# Supply.net
KiCad netlist of a schematic drawn in Altium Designer
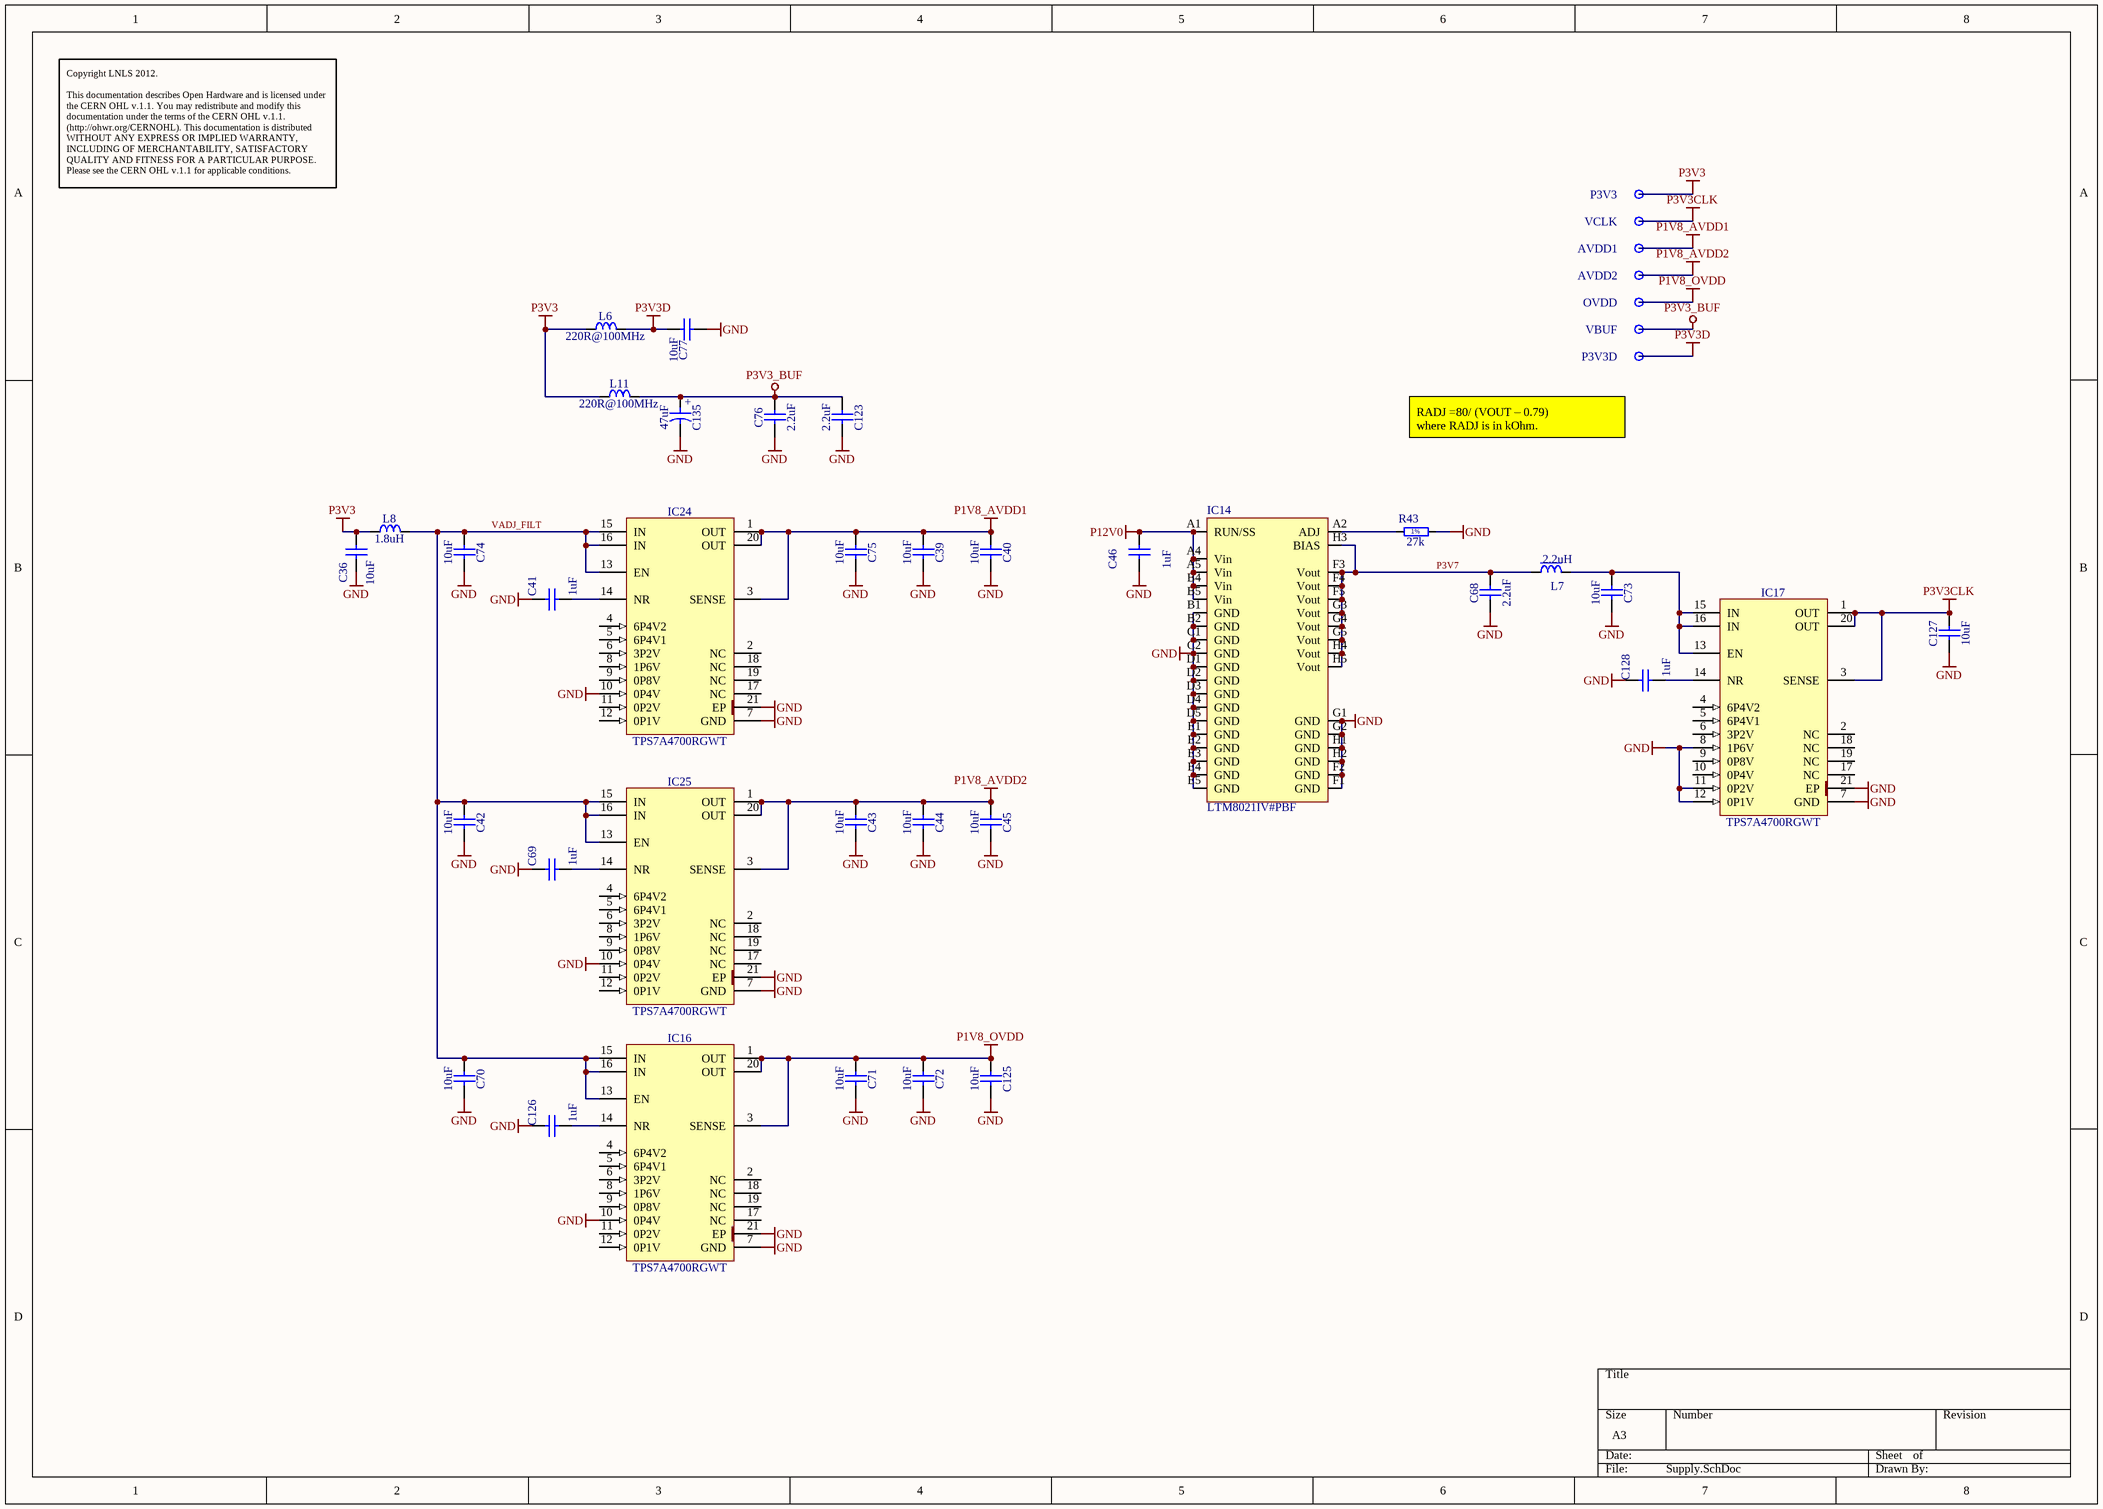
[diagram p0: Supply.SchDoc]

(export (version "E")
  (design (tool "Eeschema 10.0.6"))
  (components
    (comp (ref "AVDD1")
      (value "Test Point")
      (footprint "TPS127")
      (fields (field (name "PART NUMBER") "SMD_PAD_1.27X1.27MM") (field (name "AUTHOR") "CERN DEM JLC"))
      (libsource (lib "Eletro-mechanical") (part "Test Point"))
    )
    (comp (ref "AVDD2")
      (value "Test Point")
      (footprint "TPS127")
      (fields (field (name "PART NUMBER") "SMD_PAD_1.27X1.27MM") (field (name "AUTHOR") "CERN DEM JLC"))
      (libsource (lib "Eletro-mechanical") (part "Test Point"))
    )
    (comp (ref "C36")
      (value "10uF")
      (footprint "CAPC2012X135N")
      (description "Non-polarised capacitor")
      (fields
        (field (name "PART NUMBER") "CC0805_10UF_16V_10%_X5R")
        (field (name "VOLTAGE") "16V")
        (field (name "AUTHOR") "CERN DEM JLC")
      )
      (libsource (lib "Capacitors") (part "Capacitor - non polarized"))
    )
    (comp (ref "C39")
      (value "10uF")
      (footprint "CAPC2012X135N")
      (description "Non-polarised capacitor")
      (fields
        (field (name "PART NUMBER") "CC0805_10UF_16V_10%_X5R")
        (field (name "VOLTAGE") "16V")
        (field (name "AUTHOR") "CERN DEM JLC")
      )
      (libsource (lib "Capacitors") (part "Capacitor - non polarized"))
    )
    (comp (ref "C40")
      (value "10uF")
      (footprint "CAPC2012X135N")
      (description "Non-polarised capacitor")
      (fields
        (field (name "PART NUMBER") "CC0805_10UF_16V_10%_X5R")
        (field (name "VOLTAGE") "16V")
        (field (name "AUTHOR") "CERN DEM JLC")
      )
      (libsource (lib "Capacitors") (part "Capacitor - non polarized"))
    )
    (comp (ref "C41")
      (value "1uF")
      (footprint "CAPC1608X87N")
      (description "Non-polarised capacitor")
      (fields
        (field (name "PART NUMBER") "CC0603_1UF_16V_10%_X7R")
        (field (name "VOLTAGE") "16V")
        (field (name "AUTHOR") "CERN DEM JLC")
      )
      (libsource (lib "Capacitors") (part "Capacitor - non polarized"))
    )
    (comp (ref "C42")
      (value "10uF")
      (footprint "CAPC2012X135N")
      (description "Non-polarised capacitor")
      (fields
        (field (name "PART NUMBER") "CC0805_10UF_16V_10%_X5R")
        (field (name "VOLTAGE") "16V")
        (field (name "AUTHOR") "CERN DEM JLC")
      )
      (libsource (lib "Capacitors") (part "Capacitor - non polarized"))
    )
    (comp (ref "C43")
      (value "10uF")
      (footprint "CAPC2012X135N")
      (description "Non-polarised capacitor")
      (fields
        (field (name "PART NUMBER") "CC0805_10UF_16V_10%_X5R")
        (field (name "VOLTAGE") "16V")
        (field (name "AUTHOR") "CERN DEM JLC")
      )
      (libsource (lib "Capacitors") (part "Capacitor - non polarized"))
    )
    (comp (ref "C44")
      (value "10uF")
      (footprint "CAPC2012X135N")
      (description "Non-polarised capacitor")
      (fields
        (field (name "PART NUMBER") "CC0805_10UF_16V_10%_X5R")
        (field (name "VOLTAGE") "16V")
        (field (name "AUTHOR") "CERN DEM JLC")
      )
      (libsource (lib "Capacitors") (part "Capacitor - non polarized"))
    )
    (comp (ref "C45")
      (value "10uF")
      (footprint "CAPC2012X135N")
      (description "Non-polarised capacitor")
      (fields
        (field (name "PART NUMBER") "CC0805_10UF_16V_10%_X5R")
        (field (name "VOLTAGE") "16V")
        (field (name "AUTHOR") "CERN DEM JLC")
      )
      (libsource (lib "Capacitors") (part "Capacitor - non polarized"))
    )
    (comp (ref "C46")
      (value "1uF")
      (footprint "CAPC1608X87N")
      (description "Non-polarised capacitor")
      (fields
        (field (name "PART NUMBER") "CC0603_1UF_16V_10%_X7R")
        (field (name "VOLTAGE") "16V")
        (field (name "AUTHOR") "CERN DEM JLC")
      )
      (libsource (lib "Capacitors") (part "Capacitor - non polarized"))
    )
    (comp (ref "C68")
      (value "2.2uF")
      (footprint "CAPC2012X135N")
      (description "Non-polarised capacitor")
      (fields
        (field (name "PART NUMBER") "CC0805_2.2UF_16V_10%_X7R")
        (field (name "VOLTAGE") "16V")
        (field (name "AUTHOR") "CERN DEM JLC")
      )
      (libsource (lib "Capacitors") (part "Capacitor - non polarized"))
    )
    (comp (ref "C69")
      (value "1uF")
      (footprint "CAPC1608X87N")
      (description "Non-polarised capacitor")
      (fields
        (field (name "PART NUMBER") "CC0603_1UF_16V_10%_X7R")
        (field (name "VOLTAGE") "16V")
        (field (name "AUTHOR") "CERN DEM JLC")
      )
      (libsource (lib "Capacitors") (part "Capacitor - non polarized"))
    )
    (comp (ref "C70")
      (value "10uF")
      (footprint "CAPC2012X135N")
      (description "Non-polarised capacitor")
      (fields
        (field (name "PART NUMBER") "CC0805_10UF_16V_10%_X5R")
        (field (name "VOLTAGE") "16V")
        (field (name "AUTHOR") "CERN DEM JLC")
      )
      (libsource (lib "Capacitors") (part "Capacitor - non polarized"))
    )
    (comp (ref "C71")
      (value "10uF")
      (footprint "CAPC2012X135N")
      (description "Non-polarised capacitor")
      (fields
        (field (name "PART NUMBER") "CC0805_10UF_16V_10%_X5R")
        (field (name "VOLTAGE") "16V")
        (field (name "AUTHOR") "CERN DEM JLC")
      )
      (libsource (lib "Capacitors") (part "Capacitor - non polarized"))
    )
    (comp (ref "C72")
      (value "10uF")
      (footprint "CAPC2012X135N")
      (description "Non-polarised capacitor")
      (fields
        (field (name "PART NUMBER") "CC0805_10UF_16V_10%_X5R")
        (field (name "VOLTAGE") "16V")
        (field (name "AUTHOR") "CERN DEM JLC")
      )
      (libsource (lib "Capacitors") (part "Capacitor - non polarized"))
    )
    (comp (ref "C73")
      (value "10uF")
      (footprint "CAPC2012X135N")
      (description "Non-polarised capacitor")
      (fields
        (field (name "PART NUMBER") "CC0805_10UF_16V_10%_X5R")
        (field (name "VOLTAGE") "16V")
        (field (name "AUTHOR") "CERN DEM JLC")
      )
      (libsource (lib "Capacitors") (part "Capacitor - non polarized"))
    )
    (comp (ref "C74")
      (value "10uF")
      (footprint "CAPC2012X135N")
      (description "Non-polarised capacitor")
      (fields
        (field (name "PART NUMBER") "CC0805_10UF_16V_10%_X5R")
        (field (name "VOLTAGE") "16V")
        (field (name "AUTHOR") "CERN DEM JLC")
      )
      (libsource (lib "Capacitors") (part "Capacitor - non polarized"))
    )
    (comp (ref "C75")
      (value "10uF")
      (footprint "CAPC2012X135N")
      (description "Non-polarised capacitor")
      (fields
        (field (name "PART NUMBER") "CC0805_10UF_16V_10%_X5R")
        (field (name "VOLTAGE") "16V")
        (field (name "AUTHOR") "CERN DEM JLC")
      )
      (libsource (lib "Capacitors") (part "Capacitor - non polarized"))
    )
    (comp (ref "C76")
      (value "2.2uF")
      (footprint "CAPC2012X135N")
      (description "Non-polarised capacitor")
      (fields
        (field (name "PART NUMBER") "CC0805_2.2UF_16V_10%_X7R")
        (field (name "VOLTAGE") "16V")
        (field (name "AUTHOR") "CERN DEM JLC")
      )
      (libsource (lib "Capacitors") (part "Capacitor - non polarized"))
    )
    (comp (ref "C77")
      (value "10uF")
      (footprint "CAPC2012X135N")
      (description "Non-polarised capacitor")
      (fields
        (field (name "PART NUMBER") "CC0805_10UF_16V_10%_X5R")
        (field (name "VOLTAGE") "16V")
        (field (name "AUTHOR") "CERN DEM JLC")
      )
      (libsource (lib "Capacitors") (part "Capacitor - non polarized"))
    )
    (comp (ref "C123")
      (value "2.2uF")
      (footprint "CAPC2012X135N")
      (description "Non-polarised capacitor")
      (fields
        (field (name "PART NUMBER") "CC0805_2.2UF_16V_10%_X7R")
        (field (name "VOLTAGE") "16V")
        (field (name "AUTHOR") "CERN DEM JLC")
      )
      (libsource (lib "Capacitors") (part "Capacitor - non polarized"))
    )
    (comp (ref "C125")
      (value "10uF")
      (footprint "CAPC2012X135N")
      (description "Non-polarised capacitor")
      (fields
        (field (name "PART NUMBER") "CC0805_10UF_16V_10%_X5R")
        (field (name "VOLTAGE") "16V")
        (field (name "AUTHOR") "CERN DEM JLC")
      )
      (libsource (lib "Capacitors") (part "Capacitor - non polarized"))
    )
    (comp (ref "C126")
      (value "1uF")
      (footprint "CAPC1608X87N")
      (description "Non-polarised capacitor")
      (fields
        (field (name "PART NUMBER") "CC0603_1UF_16V_10%_X7R")
        (field (name "VOLTAGE") "16V")
        (field (name "AUTHOR") "CERN DEM JLC")
      )
      (libsource (lib "Capacitors") (part "Capacitor - non polarized"))
    )
    (comp (ref "C127")
      (value "10uF")
      (footprint "CAPC2012X135N")
      (description "Non-polarised capacitor")
      (fields
        (field (name "PART NUMBER") "CC0805_10UF_16V_10%_X5R")
        (field (name "VOLTAGE") "16V")
        (field (name "AUTHOR") "CERN DEM JLC")
      )
      (libsource (lib "Capacitors") (part "Capacitor - non polarized"))
    )
    (comp (ref "C128")
      (value "1uF")
      (footprint "CAPC1608X87N")
      (description "Non-polarised capacitor")
      (fields
        (field (name "PART NUMBER") "CC0603_1UF_16V_10%_X7R")
        (field (name "VOLTAGE") "16V")
        (field (name "AUTHOR") "CERN DEM JLC")
      )
      (libsource (lib "Capacitors") (part "Capacitor - non polarized"))
    )
    (comp (ref "C135")
      (value "47uF")
      (footprint "CAPMP3528X210N")
      (description "Polarised capacitor")
      (fields
        (field (name "PART NUMBER") "CTE3528-21_47UF_6.3V_10%_LESR0250")
        (field (name "VOLTAGE") "6.3V")
        (field (name "AUTHOR") "CERN DEM JLC")
      )
      (libsource (lib "Capacitors") (part "Capacitor - polarized"))
    )
    (comp (ref "IC14")
      (value "LTM8021IV#PBF")
      (footprint "LGA35S127P5X8_625x1125x292")
      (description "36VIN, 500mA  Step-Down DC/DC Module")
      (fields (field (name "MANUFACTURER") "LINEAR TECHNOLOGY") (field (name "AUTHOR") "LNLS DIG GBMB"))
      (libsource (lib "ICs And Semiconductors_LNLS") (part "DCDC_LINEAR_LTM8021"))
    )
    (comp (ref "IC16")
      (value "TPS7A4700RGWT")
      (footprint "QFN65P500X500X100-21N-S325")
      (description "Low Noise (3uVrms), 1A, High Voltage Low-Dropout Linear Regulator")
      (fields (field (name "MANUFACTURER") "TEXAS INSTRUMENTS") (field (name "AUTHOR") "CERN DEM JLC"))
      (libsource (lib "ICs And Semiconductors") (part "TPS7A4700RGW"))
    )
    (comp (ref "IC17")
      (value "TPS7A4700RGWT")
      (footprint "QFN65P500X500X100-21N-S325")
      (description "Low Noise (3uVrms), 1A, High Voltage Low-Dropout Linear Regulator")
      (fields (field (name "MANUFACTURER") "TEXAS INSTRUMENTS") (field (name "AUTHOR") "CERN DEM JLC"))
      (libsource (lib "ICs And Semiconductors") (part "TPS7A4700RGW"))
    )
    (comp (ref "IC24")
      (value "TPS7A4700RGWT")
      (footprint "QFN65P500X500X100-21N-S325")
      (description "Low Noise (3uVrms), 1A, High Voltage Low-Dropout Linear Regulator")
      (fields (field (name "MANUFACTURER") "TEXAS INSTRUMENTS") (field (name "AUTHOR") "CERN DEM JLC"))
      (libsource (lib "ICs And Semiconductors") (part "TPS7A4700RGW"))
    )
    (comp (ref "IC25")
      (value "TPS7A4700RGWT")
      (footprint "QFN65P500X500X100-21N-S325")
      (description "Low Noise (3uVrms), 1A, High Voltage Low-Dropout Linear Regulator")
      (fields (field (name "MANUFACTURER") "TEXAS INSTRUMENTS") (field (name "AUTHOR") "CERN DEM JLC"))
      (libsource (lib "ICs And Semiconductors") (part "TPS7A4700RGW"))
    )
    (comp (ref "L6")
      (value "220R@100MHz")
      (footprint "INDC2012X105N")
      (description "Inductor")
      (fields
        (field (name "PART NUMBER") "IND0805_MURATA_BLM21PG221SN1D")
        (field (name "POWER") "2A")
        (field (name "AUTHOR") "CERN DEM JLC")
      )
      (libsource (lib "Inductors & Transformers") (part "Inductor"))
    )
    (comp (ref "L7")
      (value "2.2uH")
      (footprint "IND_PANASONIC_ELLVGG")
      (description "Inductor With Core")
      (fields
        (field (name "PART NUMBER") "IND_2.2UH_30%_PANASONIC_ELLVGG2R2N")
        (field (name "POWER") "1.4A")
        (field (name "AUTHOR") "LNLS DIG GBMB")
      )
      (libsource (lib "Inductors & Transformers_LNLS") (part "Inductor With Magnetic core"))
    )
    (comp (ref "L8")
      (value "1.8uH")
      (footprint "IND_TDK_VLCF4020-1-1.8uH")
      (description "Inductor")
      (fields
        (field (name "PART NUMBER") "IND_1.8UH_30%_TDK_VLCF4020-1")
        (field (name "POWER") "1.9A")
        (field (name "AUTHOR") "LNLS DIG LOS")
      )
      (libsource (lib "Inductors & Transformers_LNLS") (part "Inductor"))
    )
    (comp (ref "L11")
      (value "220R@100MHz")
      (footprint "INDC2012X105N")
      (description "Inductor")
      (fields
        (field (name "PART NUMBER") "IND0805_MURATA_BLM21PG221SN1D")
        (field (name "POWER") "2A")
        (field (name "AUTHOR") "CERN DEM JLC")
      )
      (libsource (lib "Inductors & Transformers") (part "Inductor"))
    )
    (comp (ref "OVDD")
      (value "Test Point")
      (footprint "TPS127")
      (fields (field (name "PART NUMBER") "SMD_PAD_1.27X1.27MM") (field (name "AUTHOR") "CERN DEM JLC"))
      (libsource (lib "Eletro-mechanical") (part "Test Point"))
    )
    (comp (ref "P3V3")
      (value "Test Point")
      (footprint "TPS127")
      (fields (field (name "PART NUMBER") "SMD_PAD_1.27X1.27MM") (field (name "AUTHOR") "CERN DEM JLC"))
      (libsource (lib "Eletro-mechanical") (part "Test Point"))
    )
    (comp (ref "P3V3D")
      (value "Test Point")
      (footprint "TPS127")
      (fields (field (name "PART NUMBER") "SMD_PAD_1.27X1.27MM") (field (name "AUTHOR") "CERN DEM JLC"))
      (libsource (lib "Eletro-mechanical") (part "Test Point"))
    )
    (comp (ref "R43")
      (value "27k")
      (footprint "RESC1608X55N")
      (description "Resistor - 1%")
      (fields
        (field (name "PART NUMBER") "R0603_27K_1%_0.1W_100PPM")
        (field (name "POWER") "0.1W")
        (field (name "AUTHOR") "CERN DEM JLC")
      )
      (libsource (lib "Resistors") (part "Resistor - 1%"))
    )
    (comp (ref "VBUF")
      (value "Test Point")
      (footprint "TPS127")
      (fields (field (name "PART NUMBER") "SMD_PAD_1.27X1.27MM") (field (name "AUTHOR") "CERN DEM JLC"))
      (libsource (lib "Eletro-mechanical") (part "Test Point"))
    )
    (comp (ref "VCLK")
      (value "Test Point")
      (footprint "TPS127")
      (fields (field (name "PART NUMBER") "SMD_PAD_1.27X1.27MM") (field (name "AUTHOR") "CERN DEM JLC"))
      (libsource (lib "Eletro-mechanical") (part "Test Point"))
    )
  )
  (nets
    (net (code "1") (name "/P3V7") (class "Default")
      (node (ref "C68") (pin "2") (pinfunction "2_2") (pintype "passive"))
      (node (ref "IC14") (pin "F3") (pinfunction "Vout_F3") (pintype "passive"))
      (node (ref "IC14") (pin "F4") (pinfunction "Vout_F4") (pintype "passive"))
      (node (ref "IC14") (pin "F5") (pinfunction "Vout_F5") (pintype "passive"))
      (node (ref "IC14") (pin "G3") (pinfunction "Vout_G3") (pintype "passive"))
      (node (ref "IC14") (pin "G4") (pinfunction "Vout_G4") (pintype "passive"))
      (node (ref "IC14") (pin "G5") (pinfunction "Vout_G5") (pintype "passive"))
      (node (ref "IC14") (pin "H3") (pinfunction "BIAS_H3") (pintype "power_in"))
      (node (ref "IC14") (pin "H4") (pinfunction "Vout_H4") (pintype "passive"))
      (node (ref "IC14") (pin "H5") (pinfunction "Vout_H5") (pintype "passive"))
      (node (ref "L7") (pin "1") (pinfunction "1_1") (pintype "passive"))
    )
    (net (code "2") (name "/VADJ_FILT") (class "Default")
      (node (ref "C42") (pin "1") (pinfunction "1_1") (pintype "passive"))
      (node (ref "C70") (pin "1") (pinfunction "1_1") (pintype "passive"))
      (node (ref "C74") (pin "1") (pinfunction "1_1") (pintype "passive"))
      (node (ref "IC16") (pin "13") (pinfunction "EN_13") (pintype "passive"))
      (node (ref "IC16") (pin "15") (pinfunction "IN_15") (pintype "power_in"))
      (node (ref "IC16") (pin "16") (pinfunction "IN_16") (pintype "power_in"))
      (node (ref "IC24") (pin "13") (pinfunction "EN_13") (pintype "passive"))
      (node (ref "IC24") (pin "15") (pinfunction "IN_15") (pintype "power_in"))
      (node (ref "IC24") (pin "16") (pinfunction "IN_16") (pintype "power_in"))
      (node (ref "IC25") (pin "13") (pinfunction "EN_13") (pintype "passive"))
      (node (ref "IC25") (pin "15") (pinfunction "IN_15") (pintype "power_in"))
      (node (ref "IC25") (pin "16") (pinfunction "IN_16") (pintype "power_in"))
      (node (ref "L8") (pin "2") (pinfunction "2_2") (pintype "passive"))
    )
    (net (code "3") (name "GND") (class "Default")
      (node (ref "C123") (pin "2") (pinfunction "2_2") (pintype "passive"))
      (node (ref "C125") (pin "2") (pinfunction "2_2") (pintype "passive"))
      (node (ref "C126") (pin "2") (pinfunction "2_2") (pintype "passive"))
      (node (ref "C127") (pin "1") (pinfunction "1_1") (pintype "passive"))
      (node (ref "C128") (pin "2") (pinfunction "2_2") (pintype "passive"))
      (node (ref "C135") (pin "2") (pinfunction "2_2") (pintype "passive"))
      (node (ref "C36") (pin "2") (pinfunction "2_2") (pintype "passive"))
      (node (ref "C39") (pin "2") (pinfunction "2_2") (pintype "passive"))
      (node (ref "C40") (pin "2") (pinfunction "2_2") (pintype "passive"))
      (node (ref "C41") (pin "2") (pinfunction "2_2") (pintype "passive"))
      (node (ref "C42") (pin "2") (pinfunction "2_2") (pintype "passive"))
      (node (ref "C43") (pin "2") (pinfunction "2_2") (pintype "passive"))
      (node (ref "C44") (pin "2") (pinfunction "2_2") (pintype "passive"))
      (node (ref "C45") (pin "2") (pinfunction "2_2") (pintype "passive"))
      (node (ref "C46") (pin "2") (pinfunction "2_2") (pintype "passive"))
      (node (ref "C68") (pin "1") (pinfunction "1_1") (pintype "passive"))
      (node (ref "C69") (pin "2") (pinfunction "2_2") (pintype "passive"))
      (node (ref "C70") (pin "2") (pinfunction "2_2") (pintype "passive"))
      (node (ref "C71") (pin "2") (pinfunction "2_2") (pintype "passive"))
      (node (ref "C72") (pin "2") (pinfunction "2_2") (pintype "passive"))
      (node (ref "C73") (pin "2") (pinfunction "2_2") (pintype "passive"))
      (node (ref "C74") (pin "2") (pinfunction "2_2") (pintype "passive"))
      (node (ref "C75") (pin "2") (pinfunction "2_2") (pintype "passive"))
      (node (ref "C76") (pin "1") (pinfunction "1_1") (pintype "passive"))
      (node (ref "C77") (pin "2") (pinfunction "2_2") (pintype "passive"))
      (node (ref "IC14") (pin "B1") (pinfunction "GND_B1") (pintype "power_in"))
      (node (ref "IC14") (pin "B2") (pinfunction "GND_B2") (pintype "power_in"))
      (node (ref "IC14") (pin "C1") (pinfunction "GND_C1") (pintype "power_in"))
      (node (ref "IC14") (pin "C2") (pinfunction "GND_C2") (pintype "power_in"))
      (node (ref "IC14") (pin "D1") (pinfunction "GND_D1") (pintype "power_in"))
      (node (ref "IC14") (pin "D2") (pinfunction "GND_D2") (pintype "power_in"))
      (node (ref "IC14") (pin "D3") (pinfunction "GND_D3") (pintype "power_in"))
      (node (ref "IC14") (pin "D4") (pinfunction "GND_D4") (pintype "power_in"))
      (node (ref "IC14") (pin "D5") (pinfunction "GND_D5") (pintype "power_in"))
      (node (ref "IC14") (pin "E1") (pinfunction "GND_E1") (pintype "power_in"))
      (node (ref "IC14") (pin "E2") (pinfunction "GND_E2") (pintype "power_in"))
      (node (ref "IC14") (pin "E3") (pinfunction "GND_E3") (pintype "power_in"))
      (node (ref "IC14") (pin "E4") (pinfunction "GND_E4") (pintype "power_in"))
      (node (ref "IC14") (pin "E5") (pinfunction "GND_E5") (pintype "power_in"))
      (node (ref "IC14") (pin "F1") (pinfunction "GND_F1") (pintype "power_in"))
      (node (ref "IC14") (pin "F2") (pinfunction "GND_F2") (pintype "power_in"))
      (node (ref "IC14") (pin "G1") (pinfunction "GND_G1") (pintype "power_in"))
      (node (ref "IC14") (pin "G2") (pinfunction "GND_G2") (pintype "power_in"))
      (node (ref "IC14") (pin "H1") (pinfunction "GND_H1") (pintype "power_in"))
      (node (ref "IC14") (pin "H2") (pinfunction "GND_H2") (pintype "power_in"))
      (node (ref "IC16") (pin "10") (pinfunction "0P4V_10") (pintype "input"))
      (node (ref "IC16") (pin "21") (pinfunction "EP_21") (pintype "power_in"))
      (node (ref "IC16") (pin "7") (pinfunction "GND_7") (pintype "power_in"))
      (node (ref "IC17") (pin "11") (pinfunction "0P2V_11") (pintype "input"))
      (node (ref "IC17") (pin "12") (pinfunction "0P1V_12") (pintype "input"))
      (node (ref "IC17") (pin "21") (pinfunction "EP_21") (pintype "power_in"))
      (node (ref "IC17") (pin "7") (pinfunction "GND_7") (pintype "power_in"))
      (node (ref "IC17") (pin "8") (pinfunction "1P6V_8") (pintype "input"))
      (node (ref "IC24") (pin "10") (pinfunction "0P4V_10") (pintype "input"))
      (node (ref "IC24") (pin "21") (pinfunction "EP_21") (pintype "power_in"))
      (node (ref "IC24") (pin "7") (pinfunction "GND_7") (pintype "power_in"))
      (node (ref "IC25") (pin "10") (pinfunction "0P4V_10") (pintype "input"))
      (node (ref "IC25") (pin "21") (pinfunction "EP_21") (pintype "power_in"))
      (node (ref "IC25") (pin "7") (pinfunction "GND_7") (pintype "power_in"))
      (node (ref "R43") (pin "2") (pinfunction "2_2") (pintype "passive"))
    )
    (net (code "4") (name "Net-(IC14-ADJ)") (class "Default")
      (node (ref "IC14") (pin "A2") (pinfunction "ADJ_A2") (pintype "passive"))
      (node (ref "R43") (pin "1") (pinfunction "1_1") (pintype "passive"))
    )
    (net (code "5") (name "Net-(IC16-NR)") (class "Default")
      (node (ref "C126") (pin "1") (pinfunction "1_1") (pintype "passive"))
      (node (ref "IC16") (pin "14") (pinfunction "NR_14") (pintype "passive"))
    )
    (net (code "6") (name "Net-(IC17-EN)") (class "Default")
      (node (ref "C73") (pin "1") (pinfunction "1_1") (pintype "passive"))
      (node (ref "IC17") (pin "13") (pinfunction "EN_13") (pintype "passive"))
      (node (ref "IC17") (pin "15") (pinfunction "IN_15") (pintype "power_in"))
      (node (ref "IC17") (pin "16") (pinfunction "IN_16") (pintype "power_in"))
      (node (ref "L7") (pin "2") (pinfunction "2_2") (pintype "passive"))
    )
    (net (code "7") (name "Net-(IC17-NR)") (class "Default")
      (node (ref "C128") (pin "1") (pinfunction "1_1") (pintype "passive"))
      (node (ref "IC17") (pin "14") (pinfunction "NR_14") (pintype "passive"))
    )
    (net (code "8") (name "Net-(IC24-NR)") (class "Default")
      (node (ref "C41") (pin "1") (pinfunction "1_1") (pintype "passive"))
      (node (ref "IC24") (pin "14") (pinfunction "NR_14") (pintype "passive"))
    )
    (net (code "9") (name "Net-(IC25-NR)") (class "Default")
      (node (ref "C69") (pin "1") (pinfunction "1_1") (pintype "passive"))
      (node (ref "IC25") (pin "14") (pinfunction "NR_14") (pintype "passive"))
    )
    (net (code "10") (name "P1V8_AVDD1") (class "Default")
      (node (ref "AVDD1") (pin "1") (pinfunction "1_1") (pintype "bidirectional"))
      (node (ref "C39") (pin "1") (pinfunction "1_1") (pintype "passive"))
      (node (ref "C40") (pin "1") (pinfunction "1_1") (pintype "passive"))
      (node (ref "C75") (pin "1") (pinfunction "1_1") (pintype "passive"))
      (node (ref "IC24") (pin "1") (pinfunction "OUT_1") (pintype "power_in"))
      (node (ref "IC24") (pin "20") (pinfunction "OUT_20") (pintype "power_in"))
      (node (ref "IC24") (pin "3") (pinfunction "SENSE_3") (pintype "passive"))
    )
    (net (code "11") (name "P1V8_AVDD2") (class "Default")
      (node (ref "AVDD2") (pin "1") (pinfunction "1_1") (pintype "bidirectional"))
      (node (ref "C43") (pin "1") (pinfunction "1_1") (pintype "passive"))
      (node (ref "C44") (pin "1") (pinfunction "1_1") (pintype "passive"))
      (node (ref "C45") (pin "1") (pinfunction "1_1") (pintype "passive"))
      (node (ref "IC25") (pin "1") (pinfunction "OUT_1") (pintype "power_in"))
      (node (ref "IC25") (pin "20") (pinfunction "OUT_20") (pintype "power_in"))
      (node (ref "IC25") (pin "3") (pinfunction "SENSE_3") (pintype "passive"))
    )
    (net (code "12") (name "P1V8_OVDD") (class "Default")
      (node (ref "C125") (pin "1") (pinfunction "1_1") (pintype "passive"))
      (node (ref "C71") (pin "1") (pinfunction "1_1") (pintype "passive"))
      (node (ref "C72") (pin "1") (pinfunction "1_1") (pintype "passive"))
      (node (ref "IC16") (pin "1") (pinfunction "OUT_1") (pintype "power_in"))
      (node (ref "IC16") (pin "20") (pinfunction "OUT_20") (pintype "power_in"))
      (node (ref "IC16") (pin "3") (pinfunction "SENSE_3") (pintype "passive"))
      (node (ref "OVDD") (pin "1") (pinfunction "1_1") (pintype "bidirectional"))
    )
    (net (code "13") (name "P3V3") (class "Default")
      (node (ref "C36") (pin "1") (pinfunction "1_1") (pintype "passive"))
      (node (ref "L11") (pin "1") (pinfunction "1_1") (pintype "passive"))
      (node (ref "L6") (pin "1") (pinfunction "1_1") (pintype "passive"))
      (node (ref "L8") (pin "1") (pinfunction "1_1") (pintype "passive"))
      (node (ref "P3V3") (pin "1") (pinfunction "1_1") (pintype "bidirectional"))
    )
    (net (code "14") (name "P3V3CLK") (class "Default")
      (node (ref "C127") (pin "2") (pinfunction "2_2") (pintype "passive"))
      (node (ref "IC17") (pin "1") (pinfunction "OUT_1") (pintype "power_in"))
      (node (ref "IC17") (pin "20") (pinfunction "OUT_20") (pintype "power_in"))
      (node (ref "IC17") (pin "3") (pinfunction "SENSE_3") (pintype "passive"))
      (node (ref "VCLK") (pin "1") (pinfunction "1_1") (pintype "bidirectional"))
    )
    (net (code "15") (name "P3V3D") (class "Default")
      (node (ref "C77") (pin "1") (pinfunction "1_1") (pintype "passive"))
      (node (ref "L6") (pin "2") (pinfunction "2_2") (pintype "passive"))
      (node (ref "P3V3D") (pin "1") (pinfunction "1_1") (pintype "bidirectional"))
    )
    (net (code "16") (name "P3V3_BUF") (class "Default")
      (node (ref "C123") (pin "1") (pinfunction "1_1") (pintype "passive"))
      (node (ref "C135") (pin "1") (pinfunction "1_1") (pintype "passive"))
      (node (ref "C76") (pin "2") (pinfunction "2_2") (pintype "passive"))
      (node (ref "L11") (pin "2") (pinfunction "2_2") (pintype "passive"))
      (node (ref "VBUF") (pin "1") (pinfunction "1_1") (pintype "bidirectional"))
    )
    (net (code "17") (name "P12V0") (class "Default")
      (node (ref "C46") (pin "1") (pinfunction "1_1") (pintype "passive"))
      (node (ref "IC14") (pin "A1") (pinfunction "RUN/SS_A1") (pintype "passive"))
      (node (ref "IC14") (pin "A4") (pinfunction "Vin_A4") (pintype "power_in"))
      (node (ref "IC14") (pin "A5") (pinfunction "Vin_A5") (pintype "power_in"))
      (node (ref "IC14") (pin "B4") (pinfunction "Vin_B4") (pintype "power_in"))
      (node (ref "IC14") (pin "B5") (pinfunction "Vin_B5") (pintype "power_in"))
    )
    (net (code "18") (name "unconnected-(IC16-0P1V-Pad12)") (class "Default")
      (node (ref "IC16") (pin "12") (pinfunction "0P1V_12") (pintype "input"))
    )
    (net (code "19") (name "unconnected-(IC16-0P2V-Pad11)") (class "Default")
      (node (ref "IC16") (pin "11") (pinfunction "0P2V_11") (pintype "input"))
    )
    (net (code "20") (name "unconnected-(IC16-0P8V-Pad9)") (class "Default")
      (node (ref "IC16") (pin "9") (pinfunction "0P8V_9") (pintype "input"))
    )
    (net (code "21") (name "unconnected-(IC16-1P6V-Pad8)") (class "Default")
      (node (ref "IC16") (pin "8") (pinfunction "1P6V_8") (pintype "input"))
    )
    (net (code "22") (name "unconnected-(IC16-3P2V-Pad6)") (class "Default")
      (node (ref "IC16") (pin "6") (pinfunction "3P2V_6") (pintype "input"))
    )
    (net (code "23") (name "unconnected-(IC16-6P4V1-Pad5)") (class "Default")
      (node (ref "IC16") (pin "5") (pinfunction "6P4V1_5") (pintype "input"))
    )
    (net (code "24") (name "unconnected-(IC16-6P4V2-Pad4)") (class "Default")
      (node (ref "IC16") (pin "4") (pinfunction "6P4V2_4") (pintype "input"))
    )
    (net (code "25") (name "unconnected-(IC16-NC-Pad2)") (class "Default")
      (node (ref "IC16") (pin "2") (pinfunction "NC_2") (pintype "passive"))
    )
    (net (code "26") (name "unconnected-(IC16-NC-Pad17)") (class "Default")
      (node (ref "IC16") (pin "17") (pinfunction "NC_17") (pintype "passive"))
    )
    (net (code "27") (name "unconnected-(IC16-NC-Pad18)") (class "Default")
      (node (ref "IC16") (pin "18") (pinfunction "NC_18") (pintype "passive"))
    )
    (net (code "28") (name "unconnected-(IC16-NC-Pad19)") (class "Default")
      (node (ref "IC16") (pin "19") (pinfunction "NC_19") (pintype "passive"))
    )
    (net (code "29") (name "unconnected-(IC17-0P4V-Pad10)") (class "Default")
      (node (ref "IC17") (pin "10") (pinfunction "0P4V_10") (pintype "input"))
    )
    (net (code "30") (name "unconnected-(IC17-0P8V-Pad9)") (class "Default")
      (node (ref "IC17") (pin "9") (pinfunction "0P8V_9") (pintype "input"))
    )
    (net (code "31") (name "unconnected-(IC17-3P2V-Pad6)") (class "Default")
      (node (ref "IC17") (pin "6") (pinfunction "3P2V_6") (pintype "input"))
    )
    (net (code "32") (name "unconnected-(IC17-6P4V1-Pad5)") (class "Default")
      (node (ref "IC17") (pin "5") (pinfunction "6P4V1_5") (pintype "input"))
    )
    (net (code "33") (name "unconnected-(IC17-6P4V2-Pad4)") (class "Default")
      (node (ref "IC17") (pin "4") (pinfunction "6P4V2_4") (pintype "input"))
    )
    (net (code "34") (name "unconnected-(IC17-NC-Pad2)") (class "Default")
      (node (ref "IC17") (pin "2") (pinfunction "NC_2") (pintype "passive"))
    )
    (net (code "35") (name "unconnected-(IC17-NC-Pad17)") (class "Default")
      (node (ref "IC17") (pin "17") (pinfunction "NC_17") (pintype "passive"))
    )
    (net (code "36") (name "unconnected-(IC17-NC-Pad18)") (class "Default")
      (node (ref "IC17") (pin "18") (pinfunction "NC_18") (pintype "passive"))
    )
    (net (code "37") (name "unconnected-(IC17-NC-Pad19)") (class "Default")
      (node (ref "IC17") (pin "19") (pinfunction "NC_19") (pintype "passive"))
    )
    (net (code "38") (name "unconnected-(IC24-0P1V-Pad12)") (class "Default")
      (node (ref "IC24") (pin "12") (pinfunction "0P1V_12") (pintype "input"))
    )
    (net (code "39") (name "unconnected-(IC24-0P2V-Pad11)") (class "Default")
      (node (ref "IC24") (pin "11") (pinfunction "0P2V_11") (pintype "input"))
    )
    (net (code "40") (name "unconnected-(IC24-0P8V-Pad9)") (class "Default")
      (node (ref "IC24") (pin "9") (pinfunction "0P8V_9") (pintype "input"))
    )
    (net (code "41") (name "unconnected-(IC24-1P6V-Pad8)") (class "Default")
      (node (ref "IC24") (pin "8") (pinfunction "1P6V_8") (pintype "input"))
    )
    (net (code "42") (name "unconnected-(IC24-3P2V-Pad6)") (class "Default")
      (node (ref "IC24") (pin "6") (pinfunction "3P2V_6") (pintype "input"))
    )
    (net (code "43") (name "unconnected-(IC24-6P4V1-Pad5)") (class "Default")
      (node (ref "IC24") (pin "5") (pinfunction "6P4V1_5") (pintype "input"))
    )
    (net (code "44") (name "unconnected-(IC24-6P4V2-Pad4)") (class "Default")
      (node (ref "IC24") (pin "4") (pinfunction "6P4V2_4") (pintype "input"))
    )
    (net (code "45") (name "unconnected-(IC24-NC-Pad2)") (class "Default")
      (node (ref "IC24") (pin "2") (pinfunction "NC_2") (pintype "passive"))
    )
    (net (code "46") (name "unconnected-(IC24-NC-Pad17)") (class "Default")
      (node (ref "IC24") (pin "17") (pinfunction "NC_17") (pintype "passive"))
    )
    (net (code "47") (name "unconnected-(IC24-NC-Pad18)") (class "Default")
      (node (ref "IC24") (pin "18") (pinfunction "NC_18") (pintype "passive"))
    )
    (net (code "48") (name "unconnected-(IC24-NC-Pad19)") (class "Default")
      (node (ref "IC24") (pin "19") (pinfunction "NC_19") (pintype "passive"))
    )
    (net (code "49") (name "unconnected-(IC25-0P1V-Pad12)") (class "Default")
      (node (ref "IC25") (pin "12") (pinfunction "0P1V_12") (pintype "input"))
    )
    (net (code "50") (name "unconnected-(IC25-0P2V-Pad11)") (class "Default")
      (node (ref "IC25") (pin "11") (pinfunction "0P2V_11") (pintype "input"))
    )
    (net (code "51") (name "unconnected-(IC25-0P8V-Pad9)") (class "Default")
      (node (ref "IC25") (pin "9") (pinfunction "0P8V_9") (pintype "input"))
    )
    (net (code "52") (name "unconnected-(IC25-1P6V-Pad8)") (class "Default")
      (node (ref "IC25") (pin "8") (pinfunction "1P6V_8") (pintype "input"))
    )
    (net (code "53") (name "unconnected-(IC25-3P2V-Pad6)") (class "Default")
      (node (ref "IC25") (pin "6") (pinfunction "3P2V_6") (pintype "input"))
    )
    (net (code "54") (name "unconnected-(IC25-6P4V1-Pad5)") (class "Default")
      (node (ref "IC25") (pin "5") (pinfunction "6P4V1_5") (pintype "input"))
    )
    (net (code "55") (name "unconnected-(IC25-6P4V2-Pad4)") (class "Default")
      (node (ref "IC25") (pin "4") (pinfunction "6P4V2_4") (pintype "input"))
    )
    (net (code "56") (name "unconnected-(IC25-NC-Pad2)") (class "Default")
      (node (ref "IC25") (pin "2") (pinfunction "NC_2") (pintype "passive"))
    )
    (net (code "57") (name "unconnected-(IC25-NC-Pad17)") (class "Default")
      (node (ref "IC25") (pin "17") (pinfunction "NC_17") (pintype "passive"))
    )
    (net (code "58") (name "unconnected-(IC25-NC-Pad18)") (class "Default")
      (node (ref "IC25") (pin "18") (pinfunction "NC_18") (pintype "passive"))
    )
    (net (code "59") (name "unconnected-(IC25-NC-Pad19)") (class "Default")
      (node (ref "IC25") (pin "19") (pinfunction "NC_19") (pintype "passive"))
    )
  )
)
